# urov_schematic_3.net
KiCad netlist of a schematic drawn in EAGLE
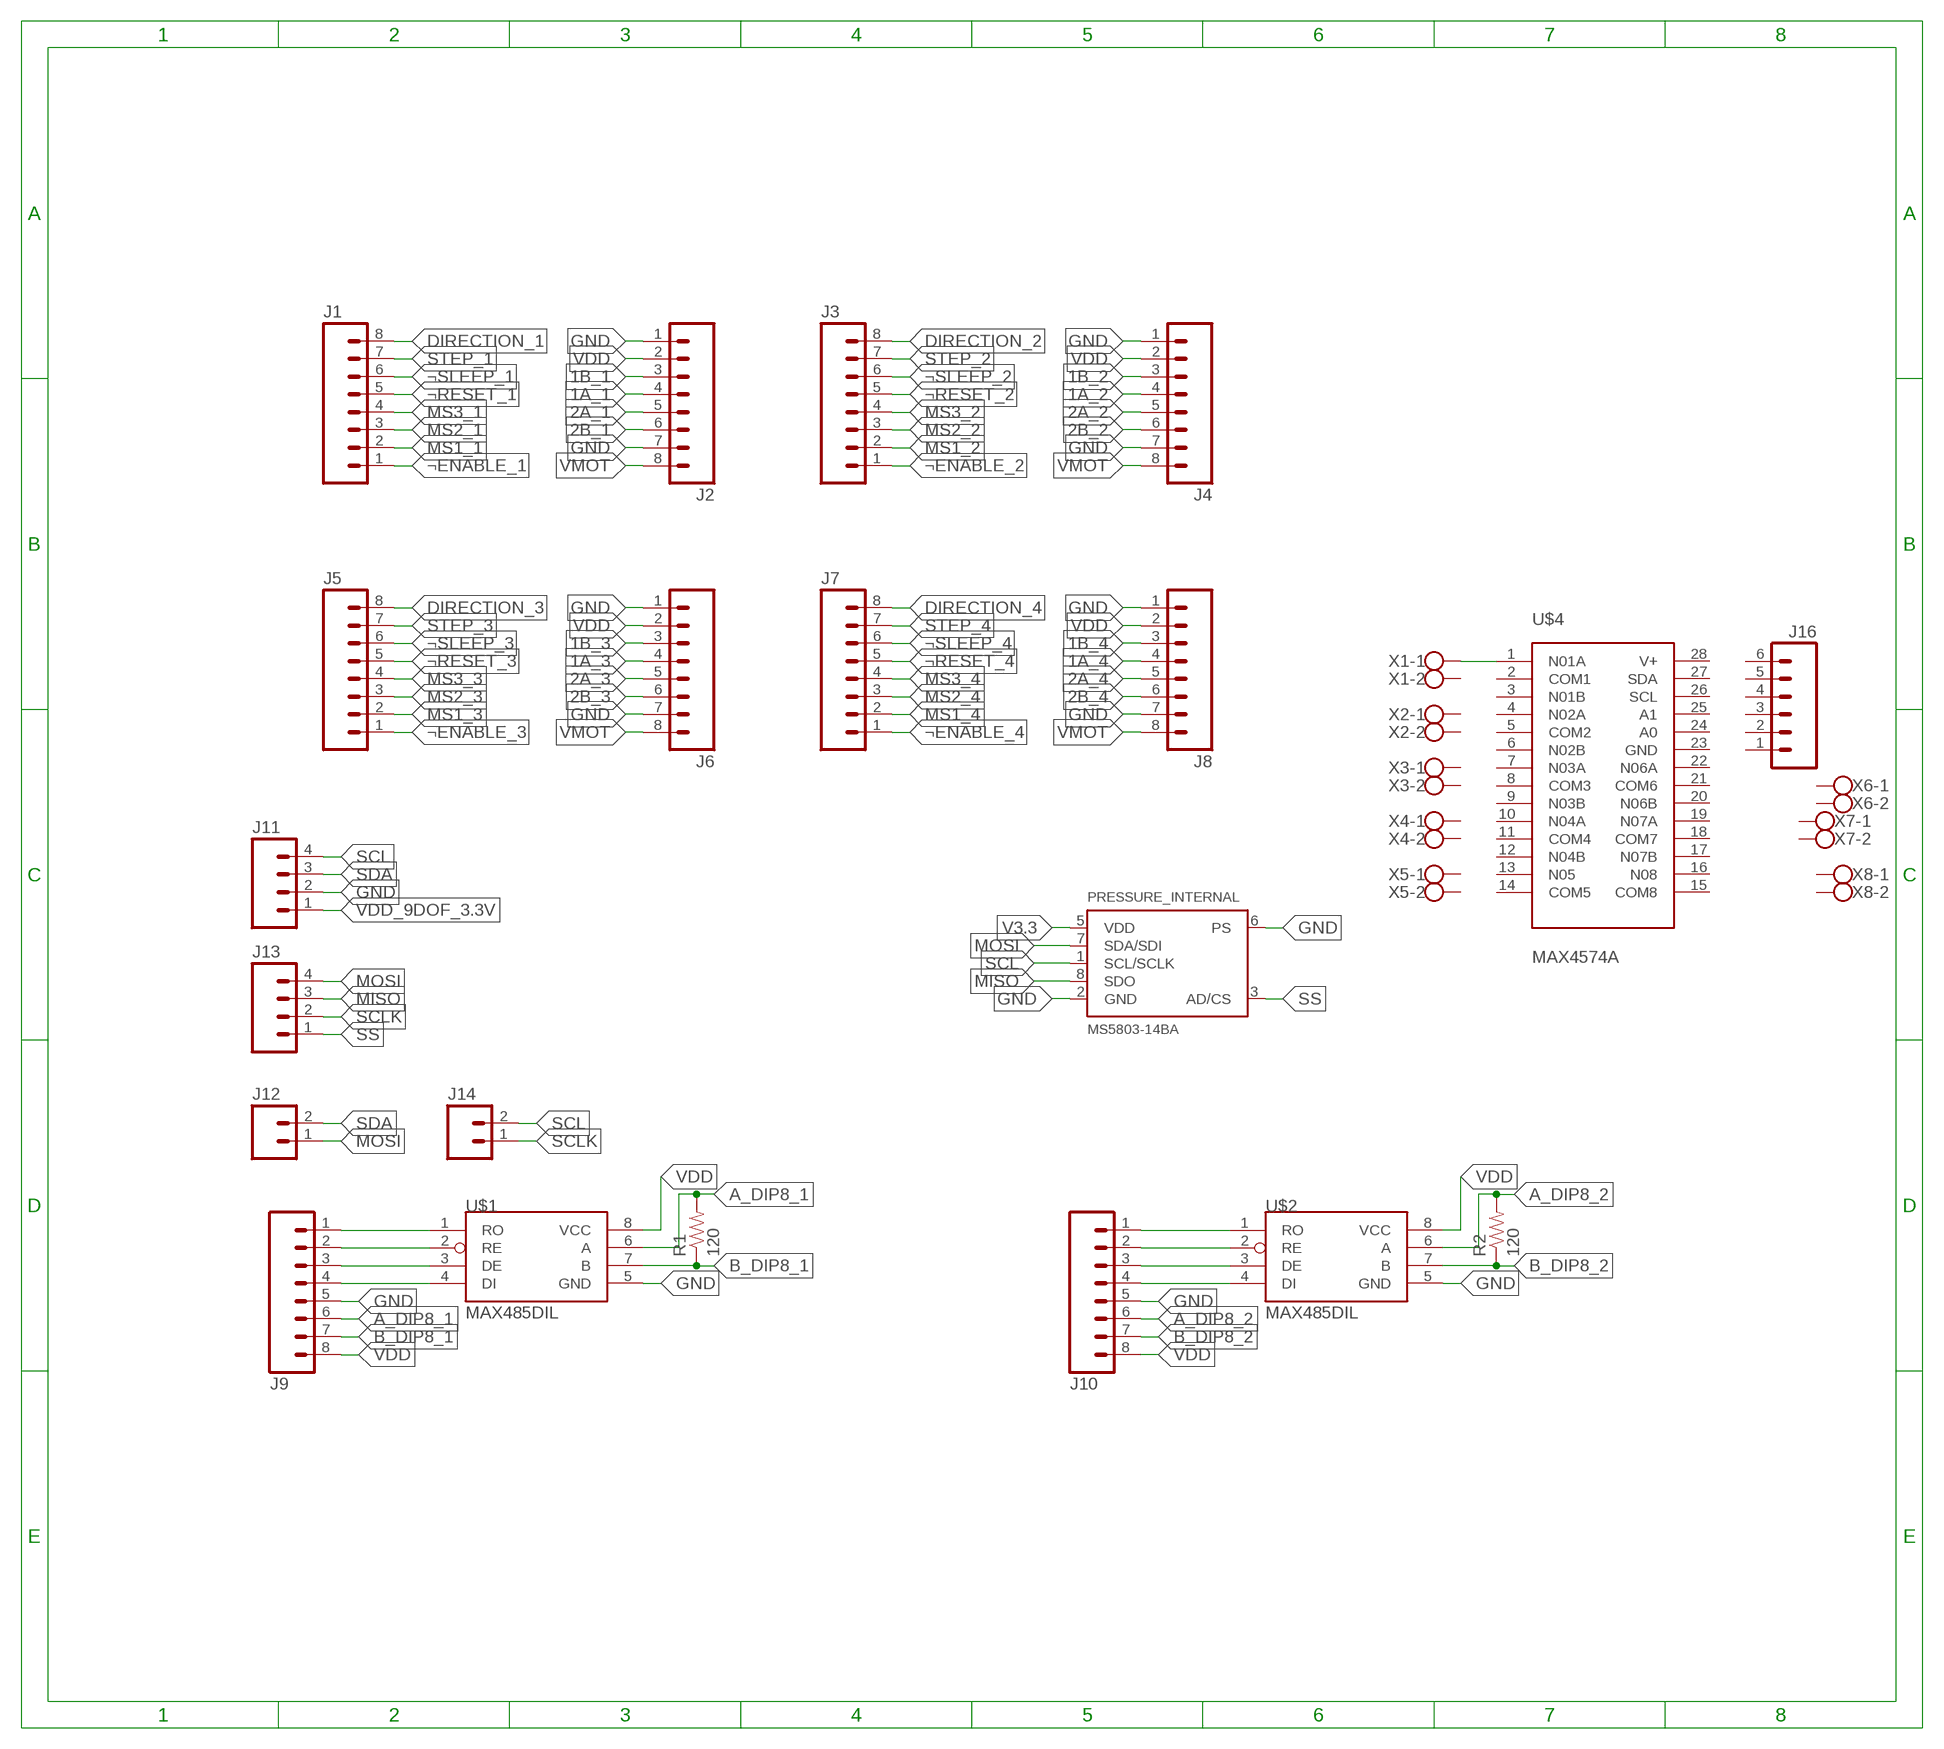
[diagram p0: schematic, sheet 1]

(export (version "E")
  (design (tool "Eeschema 10.0.6"))
  (components
    (comp (ref "J1")
      (value "M08")
      (footprint "eagle-import:1X08_ROUND")
      (libsource (lib "eagle-import") (part "M08"))
    )
    (comp (ref "J2")
      (value "M08")
      (footprint "eagle-import:1X08_ROUND")
      (libsource (lib "eagle-import") (part "M08"))
    )
    (comp (ref "J3")
      (value "M08")
      (footprint "eagle-import:1X08_ROUND")
      (libsource (lib "eagle-import") (part "M08"))
    )
    (comp (ref "J4")
      (value "M08")
      (footprint "eagle-import:1X08_ROUND")
      (libsource (lib "eagle-import") (part "M08"))
    )
    (comp (ref "J5")
      (value "M08")
      (footprint "eagle-import:1X08_ROUND")
      (libsource (lib "eagle-import") (part "M08"))
    )
    (comp (ref "J6")
      (value "M08")
      (footprint "eagle-import:1X08_ROUND")
      (libsource (lib "eagle-import") (part "M08"))
    )
    (comp (ref "J7")
      (value "M08")
      (footprint "eagle-import:1X08_ROUND")
      (libsource (lib "eagle-import") (part "M08"))
    )
    (comp (ref "J8")
      (value "M08")
      (footprint "eagle-import:1X08_ROUND")
      (libsource (lib "eagle-import") (part "M08"))
    )
    (comp (ref "J9")
      (value "M08")
      (footprint "eagle-import:1X08_ROUND")
      (libsource (lib "eagle-import") (part "M08"))
    )
    (comp (ref "J10")
      (value "M08")
      (footprint "eagle-import:1X08_ROUND")
      (libsource (lib "eagle-import") (part "M08"))
    )
    (comp (ref "J11")
      (value "M04PTH")
      (footprint "eagle-import:1X04")
      (libsource (lib "eagle-import") (part "M04PTH"))
    )
    (comp (ref "J12")
      (value "M02PTH")
      (footprint "eagle-import:1X02")
      (libsource (lib "eagle-import") (part "M02PTH"))
    )
    (comp (ref "J13")
      (value "M04PTH")
      (footprint "eagle-import:1X04")
      (libsource (lib "eagle-import") (part "M04PTH"))
    )
    (comp (ref "J14")
      (value "M02PTH")
      (footprint "eagle-import:1X02")
      (libsource (lib "eagle-import") (part "M02PTH"))
    )
    (comp (ref "J16")
      (value "M06POGOPIN_HOLES_ONLY")
      (footprint "eagle-import:1X06_HOLES_ONLY")
      (libsource (lib "eagle-import") (part "M06POGOPIN_HOLES_ONLY"))
    )
    (comp (ref "PRESSURE_INTERNAL")
      (value "MS5803-14BA")
      (footprint "eagle-import:MS5803")
      (libsource (lib "eagle-import") (part "MS5803-14BA"))
    )
    (comp (ref "R1")
      (value "120")
      (footprint "eagle-import:0805")
      (libsource (lib "eagle-import") (part "RESISTOR0805-RES"))
    )
    (comp (ref "R2")
      (value "120")
      (footprint "eagle-import:0805")
      (libsource (lib "eagle-import") (part "RESISTOR0805-RES"))
    )
    (comp (ref "U$1")
      (value "MAX485DIL")
      (footprint "eagle-import:DIL08")
      (libsource (lib "eagle-import") (part "MAX485DIL"))
    )
    (comp (ref "U$2")
      (value "MAX485DIL")
      (footprint "eagle-import:DIL08")
      (libsource (lib "eagle-import") (part "MAX485DIL"))
    )
    (comp (ref "U$4")
      (value "MAX4574A")
      (footprint "eagle-import:28-SSOP")
      (libsource (lib "eagle-import") (part "MAX4574A"))
    )
    (comp (ref "X1")
      (value "W237-102")
      (footprint "eagle-import:W237-102")
      (fields (field (name "MPN") "237-102"))
      (libsource (lib "eagle-import") (part "W237-102"))
    )
    (comp (ref "X2")
      (value "W237-102")
      (footprint "eagle-import:W237-102")
      (fields (field (name "MPN") "237-102"))
      (libsource (lib "eagle-import") (part "W237-102"))
    )
    (comp (ref "X3")
      (value "W237-102")
      (footprint "eagle-import:W237-102")
      (fields (field (name "MPN") "237-102"))
      (libsource (lib "eagle-import") (part "W237-102"))
    )
    (comp (ref "X4")
      (value "W237-102")
      (footprint "eagle-import:W237-102")
      (fields (field (name "MPN") "237-102"))
      (libsource (lib "eagle-import") (part "W237-102"))
    )
    (comp (ref "X5")
      (value "W237-102")
      (footprint "eagle-import:W237-102")
      (fields (field (name "MPN") "237-102"))
      (libsource (lib "eagle-import") (part "W237-102"))
    )
    (comp (ref "X6")
      (value "W237-102")
      (footprint "eagle-import:W237-102")
      (fields (field (name "MPN") "237-102"))
      (libsource (lib "eagle-import") (part "W237-102"))
    )
    (comp (ref "X7")
      (value "W237-102")
      (footprint "eagle-import:W237-102")
      (fields (field (name "MPN") "237-102"))
      (libsource (lib "eagle-import") (part "W237-102"))
    )
    (comp (ref "X8")
      (value "W237-102")
      (footprint "eagle-import:W237-102")
      (fields (field (name "MPN") "237-102"))
      (libsource (lib "eagle-import") (part "W237-102"))
    )
  )
  (nets
    (net (code "1") (name "1A_1") (class "Default")
      (node (ref "J2") (pin "4") (pinfunction "4_4") (pintype "passive"))
    )
    (net (code "2") (name "1A_2") (class "Default")
      (node (ref "J4") (pin "4") (pinfunction "4_4") (pintype "passive"))
    )
    (net (code "3") (name "1A_3") (class "Default")
      (node (ref "J6") (pin "4") (pinfunction "4_4") (pintype "passive"))
    )
    (net (code "4") (name "1A_4") (class "Default")
      (node (ref "J8") (pin "4") (pinfunction "4_4") (pintype "passive"))
    )
    (net (code "5") (name "1B_1") (class "Default")
      (node (ref "J2") (pin "3") (pinfunction "3_3") (pintype "passive"))
    )
    (net (code "6") (name "1B_2") (class "Default")
      (node (ref "J4") (pin "3") (pinfunction "3_3") (pintype "passive"))
    )
    (net (code "7") (name "1B_3") (class "Default")
      (node (ref "J6") (pin "3") (pinfunction "3_3") (pintype "passive"))
    )
    (net (code "8") (name "1B_4") (class "Default")
      (node (ref "J8") (pin "3") (pinfunction "3_3") (pintype "passive"))
    )
    (net (code "9") (name "2A_1") (class "Default")
      (node (ref "J2") (pin "5") (pinfunction "5_5") (pintype "passive"))
    )
    (net (code "10") (name "2A_2") (class "Default")
      (node (ref "J4") (pin "5") (pinfunction "5_5") (pintype "passive"))
    )
    (net (code "11") (name "2A_3") (class "Default")
      (node (ref "J6") (pin "5") (pinfunction "5_5") (pintype "passive"))
    )
    (net (code "12") (name "2A_4") (class "Default")
      (node (ref "J8") (pin "5") (pinfunction "5_5") (pintype "passive"))
    )
    (net (code "13") (name "2B_1") (class "Default")
      (node (ref "J2") (pin "6") (pinfunction "6_6") (pintype "passive"))
    )
    (net (code "14") (name "2B_2") (class "Default")
      (node (ref "J4") (pin "6") (pinfunction "6_6") (pintype "passive"))
    )
    (net (code "15") (name "2B_3") (class "Default")
      (node (ref "J6") (pin "6") (pinfunction "6_6") (pintype "passive"))
    )
    (net (code "16") (name "2B_4") (class "Default")
      (node (ref "J8") (pin "6") (pinfunction "6_6") (pintype "passive"))
    )
    (net (code "17") (name "A_DIP8_1") (class "Default")
      (node (ref "J9") (pin "6") (pinfunction "6_6") (pintype "passive"))
      (node (ref "R1") (pin "2") (pinfunction "2_2") (pintype "passive"))
      (node (ref "U$1") (pin "6") (pinfunction "A_6") (pintype "bidirectional"))
    )
    (net (code "18") (name "A_DIP8_2") (class "Default")
      (node (ref "J10") (pin "6") (pinfunction "6_6") (pintype "passive"))
      (node (ref "R2") (pin "2") (pinfunction "2_2") (pintype "passive"))
      (node (ref "U$2") (pin "6") (pinfunction "A_6") (pintype "bidirectional"))
    )
    (net (code "19") (name "B_DIP8_1") (class "Default")
      (node (ref "J9") (pin "7") (pinfunction "7_7") (pintype "passive"))
      (node (ref "R1") (pin "1") (pinfunction "1_1") (pintype "passive"))
      (node (ref "U$1") (pin "7") (pinfunction "B_7") (pintype "bidirectional"))
    )
    (net (code "20") (name "B_DIP8_2") (class "Default")
      (node (ref "J10") (pin "7") (pinfunction "7_7") (pintype "passive"))
      (node (ref "R2") (pin "1") (pinfunction "1_1") (pintype "passive"))
      (node (ref "U$2") (pin "7") (pinfunction "B_7") (pintype "bidirectional"))
    )
    (net (code "21") (name "DIRECTION_1") (class "Default")
      (node (ref "J1") (pin "8") (pinfunction "8_8") (pintype "passive"))
    )
    (net (code "22") (name "DIRECTION_2") (class "Default")
      (node (ref "J3") (pin "8") (pinfunction "8_8") (pintype "passive"))
    )
    (net (code "23") (name "DIRECTION_3") (class "Default")
      (node (ref "J5") (pin "8") (pinfunction "8_8") (pintype "passive"))
    )
    (net (code "24") (name "DIRECTION_4") (class "Default")
      (node (ref "J7") (pin "8") (pinfunction "8_8") (pintype "passive"))
    )
    (net (code "25") (name "GND") (class "Default")
      (node (ref "J10") (pin "5") (pinfunction "5_5") (pintype "passive"))
      (node (ref "J11") (pin "2") (pinfunction "2_2") (pintype "passive"))
      (node (ref "J2") (pin "1") (pinfunction "1_1") (pintype "passive"))
      (node (ref "J2") (pin "7") (pinfunction "7_7") (pintype "passive"))
      (node (ref "J4") (pin "1") (pinfunction "1_1") (pintype "passive"))
      (node (ref "J4") (pin "7") (pinfunction "7_7") (pintype "passive"))
      (node (ref "J6") (pin "1") (pinfunction "1_1") (pintype "passive"))
      (node (ref "J6") (pin "7") (pinfunction "7_7") (pintype "passive"))
      (node (ref "J8") (pin "1") (pinfunction "1_1") (pintype "passive"))
      (node (ref "J8") (pin "7") (pinfunction "7_7") (pintype "passive"))
      (node (ref "J9") (pin "5") (pinfunction "5_5") (pintype "passive"))
      (node (ref "PRESSURE_INTERNAL") (pin "2") (pinfunction "GND_2") (pintype "bidirectional"))
      (node (ref "PRESSURE_INTERNAL") (pin "6") (pinfunction "PS_6") (pintype "bidirectional"))
      (node (ref "U$1") (pin "5") (pinfunction "GND_5") (pintype "bidirectional"))
      (node (ref "U$2") (pin "5") (pinfunction "GND_5") (pintype "bidirectional"))
    )
    (net (code "26") (name "MISO") (class "Default")
      (node (ref "J13") (pin "3") (pinfunction "3_3") (pintype "passive"))
      (node (ref "PRESSURE_INTERNAL") (pin "8") (pinfunction "SDO_8") (pintype "bidirectional"))
    )
    (net (code "27") (name "MOSI") (class "Default")
      (node (ref "J12") (pin "1") (pinfunction "1_1") (pintype "passive"))
      (node (ref "J13") (pin "4") (pinfunction "4_4") (pintype "passive"))
      (node (ref "PRESSURE_INTERNAL") (pin "7") (pinfunction "SDA/SDI_7") (pintype "bidirectional"))
    )
    (net (code "28") (name "MS1_1") (class "Default")
      (node (ref "J1") (pin "2") (pinfunction "2_2") (pintype "passive"))
    )
    (net (code "29") (name "MS1_2") (class "Default")
      (node (ref "J3") (pin "2") (pinfunction "2_2") (pintype "passive"))
    )
    (net (code "30") (name "MS1_3") (class "Default")
      (node (ref "J5") (pin "2") (pinfunction "2_2") (pintype "passive"))
    )
    (net (code "31") (name "MS1_4") (class "Default")
      (node (ref "J7") (pin "2") (pinfunction "2_2") (pintype "passive"))
    )
    (net (code "32") (name "MS2_1") (class "Default")
      (node (ref "J1") (pin "3") (pinfunction "3_3") (pintype "passive"))
    )
    (net (code "33") (name "MS2_2") (class "Default")
      (node (ref "J3") (pin "3") (pinfunction "3_3") (pintype "passive"))
    )
    (net (code "34") (name "MS2_3") (class "Default")
      (node (ref "J5") (pin "3") (pinfunction "3_3") (pintype "passive"))
    )
    (net (code "35") (name "MS2_4") (class "Default")
      (node (ref "J7") (pin "3") (pinfunction "3_3") (pintype "passive"))
    )
    (net (code "36") (name "MS3_1") (class "Default")
      (node (ref "J1") (pin "4") (pinfunction "4_4") (pintype "passive"))
    )
    (net (code "37") (name "MS3_2") (class "Default")
      (node (ref "J3") (pin "4") (pinfunction "4_4") (pintype "passive"))
    )
    (net (code "38") (name "MS3_3") (class "Default")
      (node (ref "J5") (pin "4") (pinfunction "4_4") (pintype "passive"))
    )
    (net (code "39") (name "MS3_4") (class "Default")
      (node (ref "J7") (pin "4") (pinfunction "4_4") (pintype "passive"))
    )
    (net (code "40") (name "Net-(U$1-DE)") (class "Default")
      (node (ref "J9") (pin "3") (pinfunction "3_3") (pintype "passive"))
      (node (ref "U$1") (pin "3") (pinfunction "DE_3") (pintype "bidirectional"))
    )
    (net (code "41") (name "Net-(U$1-DI)") (class "Default")
      (node (ref "J9") (pin "4") (pinfunction "4_4") (pintype "passive"))
      (node (ref "U$1") (pin "4") (pinfunction "DI_4") (pintype "bidirectional"))
    )
    (net (code "42") (name "Net-(U$1-RE)") (class "Default")
      (node (ref "J9") (pin "2") (pinfunction "2_2") (pintype "passive"))
      (node (ref "U$1") (pin "2") (pinfunction "RE_2") (pintype "bidirectional"))
    )
    (net (code "43") (name "Net-(U$1-RO)") (class "Default")
      (node (ref "J9") (pin "1") (pinfunction "1_1") (pintype "passive"))
      (node (ref "U$1") (pin "1") (pinfunction "RO_1") (pintype "bidirectional"))
    )
    (net (code "44") (name "Net-(U$2-DE)") (class "Default")
      (node (ref "J10") (pin "3") (pinfunction "3_3") (pintype "passive"))
      (node (ref "U$2") (pin "3") (pinfunction "DE_3") (pintype "bidirectional"))
    )
    (net (code "45") (name "Net-(U$2-DI)") (class "Default")
      (node (ref "J10") (pin "4") (pinfunction "4_4") (pintype "passive"))
      (node (ref "U$2") (pin "4") (pinfunction "DI_4") (pintype "bidirectional"))
    )
    (net (code "46") (name "Net-(U$2-RE)") (class "Default")
      (node (ref "J10") (pin "2") (pinfunction "2_2") (pintype "passive"))
      (node (ref "U$2") (pin "2") (pinfunction "RE_2") (pintype "bidirectional"))
    )
    (net (code "47") (name "Net-(U$2-RO)") (class "Default")
      (node (ref "J10") (pin "1") (pinfunction "1_1") (pintype "passive"))
      (node (ref "U$2") (pin "1") (pinfunction "RO_1") (pintype "bidirectional"))
    )
    (net (code "48") (name "Net-(U$4-N01A)") (class "Default")
      (node (ref "U$4") (pin "1") (pinfunction "N01A_1") (pintype "bidirectional"))
      (node (ref "X1") (pin "1") (pinfunction "KL_1") (pintype "passive"))
    )
    (net (code "49") (name "SCL") (class "Default")
      (node (ref "J11") (pin "4") (pinfunction "4_4") (pintype "passive"))
      (node (ref "J14") (pin "2") (pinfunction "2_2") (pintype "passive"))
      (node (ref "PRESSURE_INTERNAL") (pin "1") (pinfunction "SCL/SCLK_1") (pintype "bidirectional"))
    )
    (net (code "50") (name "SCLK") (class "Default")
      (node (ref "J13") (pin "2") (pinfunction "2_2") (pintype "passive"))
      (node (ref "J14") (pin "1") (pinfunction "1_1") (pintype "passive"))
    )
    (net (code "51") (name "SDA") (class "Default")
      (node (ref "J11") (pin "3") (pinfunction "3_3") (pintype "passive"))
      (node (ref "J12") (pin "2") (pinfunction "2_2") (pintype "passive"))
    )
    (net (code "52") (name "SS") (class "Default")
      (node (ref "J13") (pin "1") (pinfunction "1_1") (pintype "passive"))
      (node (ref "PRESSURE_INTERNAL") (pin "3") (pinfunction "AD/CS_3") (pintype "bidirectional"))
    )
    (net (code "53") (name "STEP_1") (class "Default")
      (node (ref "J1") (pin "7") (pinfunction "7_7") (pintype "passive"))
    )
    (net (code "54") (name "STEP_2") (class "Default")
      (node (ref "J3") (pin "7") (pinfunction "7_7") (pintype "passive"))
    )
    (net (code "55") (name "STEP_3") (class "Default")
      (node (ref "J5") (pin "7") (pinfunction "7_7") (pintype "passive"))
    )
    (net (code "56") (name "STEP_4") (class "Default")
      (node (ref "J7") (pin "7") (pinfunction "7_7") (pintype "passive"))
    )
    (net (code "57") (name "V3.3") (class "Default")
      (node (ref "PRESSURE_INTERNAL") (pin "5") (pinfunction "VDD_5") (pintype "bidirectional"))
    )
    (net (code "58") (name "VDD") (class "Default")
      (node (ref "J10") (pin "8") (pinfunction "8_8") (pintype "passive"))
      (node (ref "J2") (pin "2") (pinfunction "2_2") (pintype "passive"))
      (node (ref "J4") (pin "2") (pinfunction "2_2") (pintype "passive"))
      (node (ref "J6") (pin "2") (pinfunction "2_2") (pintype "passive"))
      (node (ref "J8") (pin "2") (pinfunction "2_2") (pintype "passive"))
      (node (ref "J9") (pin "8") (pinfunction "8_8") (pintype "passive"))
      (node (ref "U$1") (pin "8") (pinfunction "VCC_8") (pintype "bidirectional"))
      (node (ref "U$2") (pin "8") (pinfunction "VCC_8") (pintype "bidirectional"))
    )
    (net (code "59") (name "VDD_9DOF_3.3V") (class "Default")
      (node (ref "J11") (pin "1") (pinfunction "1_1") (pintype "passive"))
    )
    (net (code "60") (name "VMOT") (class "Default")
      (node (ref "J2") (pin "8") (pinfunction "8_8") (pintype "passive"))
      (node (ref "J4") (pin "8") (pinfunction "8_8") (pintype "passive"))
      (node (ref "J6") (pin "8") (pinfunction "8_8") (pintype "passive"))
      (node (ref "J8") (pin "8") (pinfunction "8_8") (pintype "passive"))
    )
    (net (code "61") (name "unconnected-(J16-Pad1)") (class "Default")
      (node (ref "J16") (pin "1") (pinfunction "1_1") (pintype "passive"))
    )
    (net (code "62") (name "unconnected-(J16-Pad2)") (class "Default")
      (node (ref "J16") (pin "2") (pinfunction "2_2") (pintype "passive"))
    )
    (net (code "63") (name "unconnected-(J16-Pad3)") (class "Default")
      (node (ref "J16") (pin "3") (pinfunction "3_3") (pintype "passive"))
    )
    (net (code "64") (name "unconnected-(J16-Pad4)") (class "Default")
      (node (ref "J16") (pin "4") (pinfunction "4_4") (pintype "passive"))
    )
    (net (code "65") (name "unconnected-(J16-Pad5)") (class "Default")
      (node (ref "J16") (pin "5") (pinfunction "5_5") (pintype "passive"))
    )
    (net (code "66") (name "unconnected-(J16-Pad6)") (class "Default")
      (node (ref "J16") (pin "6") (pinfunction "6_6") (pintype "passive"))
    )
    (net (code "67") (name "unconnected-(U$4-A0-Pad24)") (class "Default")
      (node (ref "U$4") (pin "24") (pinfunction "A0_24") (pintype "bidirectional"))
    )
    (net (code "68") (name "unconnected-(U$4-A1-Pad25)") (class "Default")
      (node (ref "U$4") (pin "25") (pinfunction "A1_25") (pintype "bidirectional"))
    )
    (net (code "69") (name "unconnected-(U$4-COM1-Pad2)") (class "Default")
      (node (ref "U$4") (pin "2") (pinfunction "COM1_2") (pintype "bidirectional"))
    )
    (net (code "70") (name "unconnected-(U$4-COM2-Pad5)") (class "Default")
      (node (ref "U$4") (pin "5") (pinfunction "COM2_5") (pintype "bidirectional"))
    )
    (net (code "71") (name "unconnected-(U$4-COM3-Pad8)") (class "Default")
      (node (ref "U$4") (pin "8") (pinfunction "COM3_8") (pintype "bidirectional"))
    )
    (net (code "72") (name "unconnected-(U$4-COM4-Pad11)") (class "Default")
      (node (ref "U$4") (pin "11") (pinfunction "COM4_11") (pintype "bidirectional"))
    )
    (net (code "73") (name "unconnected-(U$4-COM5-Pad14)") (class "Default")
      (node (ref "U$4") (pin "14") (pinfunction "COM5_14") (pintype "bidirectional"))
    )
    (net (code "74") (name "unconnected-(U$4-COM6-Pad21)") (class "Default")
      (node (ref "U$4") (pin "21") (pinfunction "COM6_21") (pintype "bidirectional"))
    )
    (net (code "75") (name "unconnected-(U$4-COM7-Pad18)") (class "Default")
      (node (ref "U$4") (pin "18") (pinfunction "COM7_18") (pintype "bidirectional"))
    )
    (net (code "76") (name "unconnected-(U$4-COM8-Pad15)") (class "Default")
      (node (ref "U$4") (pin "15") (pinfunction "COM8_15") (pintype "bidirectional"))
    )
    (net (code "77") (name "unconnected-(U$4-GND-Pad23)") (class "Default")
      (node (ref "U$4") (pin "23") (pinfunction "GND_23") (pintype "bidirectional"))
    )
    (net (code "78") (name "unconnected-(U$4-N01B-Pad3)") (class "Default")
      (node (ref "U$4") (pin "3") (pinfunction "N01B_3") (pintype "bidirectional"))
    )
    (net (code "79") (name "unconnected-(U$4-N02A-Pad4)") (class "Default")
      (node (ref "U$4") (pin "4") (pinfunction "N02A_4") (pintype "bidirectional"))
    )
    (net (code "80") (name "unconnected-(U$4-N02B-Pad6)") (class "Default")
      (node (ref "U$4") (pin "6") (pinfunction "N02B_6") (pintype "bidirectional"))
    )
    (net (code "81") (name "unconnected-(U$4-N03A-Pad7)") (class "Default")
      (node (ref "U$4") (pin "7") (pinfunction "N03A_7") (pintype "bidirectional"))
    )
    (net (code "82") (name "unconnected-(U$4-N03B-Pad9)") (class "Default")
      (node (ref "U$4") (pin "9") (pinfunction "N03B_9") (pintype "bidirectional"))
    )
    (net (code "83") (name "unconnected-(U$4-N04A-Pad10)") (class "Default")
      (node (ref "U$4") (pin "10") (pinfunction "N04A_10") (pintype "bidirectional"))
    )
    (net (code "84") (name "unconnected-(U$4-N04B-Pad12)") (class "Default")
      (node (ref "U$4") (pin "12") (pinfunction "N04B_12") (pintype "bidirectional"))
    )
    (net (code "85") (name "unconnected-(U$4-N05-Pad13)") (class "Default")
      (node (ref "U$4") (pin "13") (pinfunction "N05_13") (pintype "bidirectional"))
    )
    (net (code "86") (name "unconnected-(U$4-N06A-Pad22)") (class "Default")
      (node (ref "U$4") (pin "22") (pinfunction "N06A_22") (pintype "bidirectional"))
    )
    (net (code "87") (name "unconnected-(U$4-N06B-Pad20)") (class "Default")
      (node (ref "U$4") (pin "20") (pinfunction "N06B_20") (pintype "bidirectional"))
    )
    (net (code "88") (name "unconnected-(U$4-N07A-Pad19)") (class "Default")
      (node (ref "U$4") (pin "19") (pinfunction "N07A_19") (pintype "bidirectional"))
    )
    (net (code "89") (name "unconnected-(U$4-N07B-Pad17)") (class "Default")
      (node (ref "U$4") (pin "17") (pinfunction "N07B_17") (pintype "bidirectional"))
    )
    (net (code "90") (name "unconnected-(U$4-N08-Pad16)") (class "Default")
      (node (ref "U$4") (pin "16") (pinfunction "N08_16") (pintype "bidirectional"))
    )
    (net (code "91") (name "unconnected-(U$4-SCL-Pad26)") (class "Default")
      (node (ref "U$4") (pin "26") (pinfunction "SCL_26") (pintype "bidirectional"))
    )
    (net (code "92") (name "unconnected-(U$4-SDA-Pad27)") (class "Default")
      (node (ref "U$4") (pin "27") (pinfunction "SDA_27") (pintype "bidirectional"))
    )
    (net (code "93") (name "unconnected-(U$4-V+-Pad28)") (class "Default")
      (node (ref "U$4") (pin "28") (pinfunction "V+_28") (pintype "bidirectional"))
    )
    (net (code "94") (name "unconnected-(X1B-KL-Pad2)") (class "Default")
      (node (ref "X1") (pin "2") (pinfunction "KL_2") (pintype "passive"))
    )
    (net (code "95") (name "unconnected-(X2A-KL-Pad1)") (class "Default")
      (node (ref "X2") (pin "1") (pinfunction "KL_1") (pintype "passive"))
    )
    (net (code "96") (name "unconnected-(X2B-KL-Pad2)") (class "Default")
      (node (ref "X2") (pin "2") (pinfunction "KL_2") (pintype "passive"))
    )
    (net (code "97") (name "unconnected-(X3A-KL-Pad1)") (class "Default")
      (node (ref "X3") (pin "1") (pinfunction "KL_1") (pintype "passive"))
    )
    (net (code "98") (name "unconnected-(X3B-KL-Pad2)") (class "Default")
      (node (ref "X3") (pin "2") (pinfunction "KL_2") (pintype "passive"))
    )
    (net (code "99") (name "unconnected-(X4A-KL-Pad1)") (class "Default")
      (node (ref "X4") (pin "1") (pinfunction "KL_1") (pintype "passive"))
    )
    (net (code "100") (name "unconnected-(X4B-KL-Pad2)") (class "Default")
      (node (ref "X4") (pin "2") (pinfunction "KL_2") (pintype "passive"))
    )
    (net (code "101") (name "unconnected-(X5A-KL-Pad1)") (class "Default")
      (node (ref "X5") (pin "1") (pinfunction "KL_1") (pintype "passive"))
    )
    (net (code "102") (name "unconnected-(X5B-KL-Pad2)") (class "Default")
      (node (ref "X5") (pin "2") (pinfunction "KL_2") (pintype "passive"))
    )
    (net (code "103") (name "unconnected-(X6A-KL-Pad1)") (class "Default")
      (node (ref "X6") (pin "1") (pinfunction "KL_1") (pintype "passive"))
    )
    (net (code "104") (name "unconnected-(X6B-KL-Pad2)") (class "Default")
      (node (ref "X6") (pin "2") (pinfunction "KL_2") (pintype "passive"))
    )
    (net (code "105") (name "unconnected-(X7A-KL-Pad1)") (class "Default")
      (node (ref "X7") (pin "1") (pinfunction "KL_1") (pintype "passive"))
    )
    (net (code "106") (name "unconnected-(X7B-KL-Pad2)") (class "Default")
      (node (ref "X7") (pin "2") (pinfunction "KL_2") (pintype "passive"))
    )
    (net (code "107") (name "unconnected-(X8A-KL-Pad1)") (class "Default")
      (node (ref "X8") (pin "1") (pinfunction "KL_1") (pintype "passive"))
    )
    (net (code "108") (name "unconnected-(X8B-KL-Pad2)") (class "Default")
      (node (ref "X8") (pin "2") (pinfunction "KL_2") (pintype "passive"))
    )
    (net (code "109") (name "¬ENABLE_1") (class "Default")
      (node (ref "J1") (pin "1") (pinfunction "1_1") (pintype "passive"))
    )
    (net (code "110") (name "¬ENABLE_2") (class "Default")
      (node (ref "J3") (pin "1") (pinfunction "1_1") (pintype "passive"))
    )
    (net (code "111") (name "¬ENABLE_3") (class "Default")
      (node (ref "J5") (pin "1") (pinfunction "1_1") (pintype "passive"))
    )
    (net (code "112") (name "¬ENABLE_4") (class "Default")
      (node (ref "J7") (pin "1") (pinfunction "1_1") (pintype "passive"))
    )
    (net (code "113") (name "¬RESET_1") (class "Default")
      (node (ref "J1") (pin "5") (pinfunction "5_5") (pintype "passive"))
    )
    (net (code "114") (name "¬RESET_2") (class "Default")
      (node (ref "J3") (pin "5") (pinfunction "5_5") (pintype "passive"))
    )
    (net (code "115") (name "¬RESET_3") (class "Default")
      (node (ref "J5") (pin "5") (pinfunction "5_5") (pintype "passive"))
    )
    (net (code "116") (name "¬RESET_4") (class "Default")
      (node (ref "J7") (pin "5") (pinfunction "5_5") (pintype "passive"))
    )
    (net (code "117") (name "¬SLEEP_1") (class "Default")
      (node (ref "J1") (pin "6") (pinfunction "6_6") (pintype "passive"))
    )
    (net (code "118") (name "¬SLEEP_2") (class "Default")
      (node (ref "J3") (pin "6") (pinfunction "6_6") (pintype "passive"))
    )
    (net (code "119") (name "¬SLEEP_3") (class "Default")
      (node (ref "J5") (pin "6") (pinfunction "6_6") (pintype "passive"))
    )
    (net (code "120") (name "¬SLEEP_4") (class "Default")
      (node (ref "J7") (pin "6") (pinfunction "6_6") (pintype "passive"))
    )
  )
)
